# SW6106_A_B_C_MCU_LED.net
KiCad netlist of a schematic drawn in Altium Designer
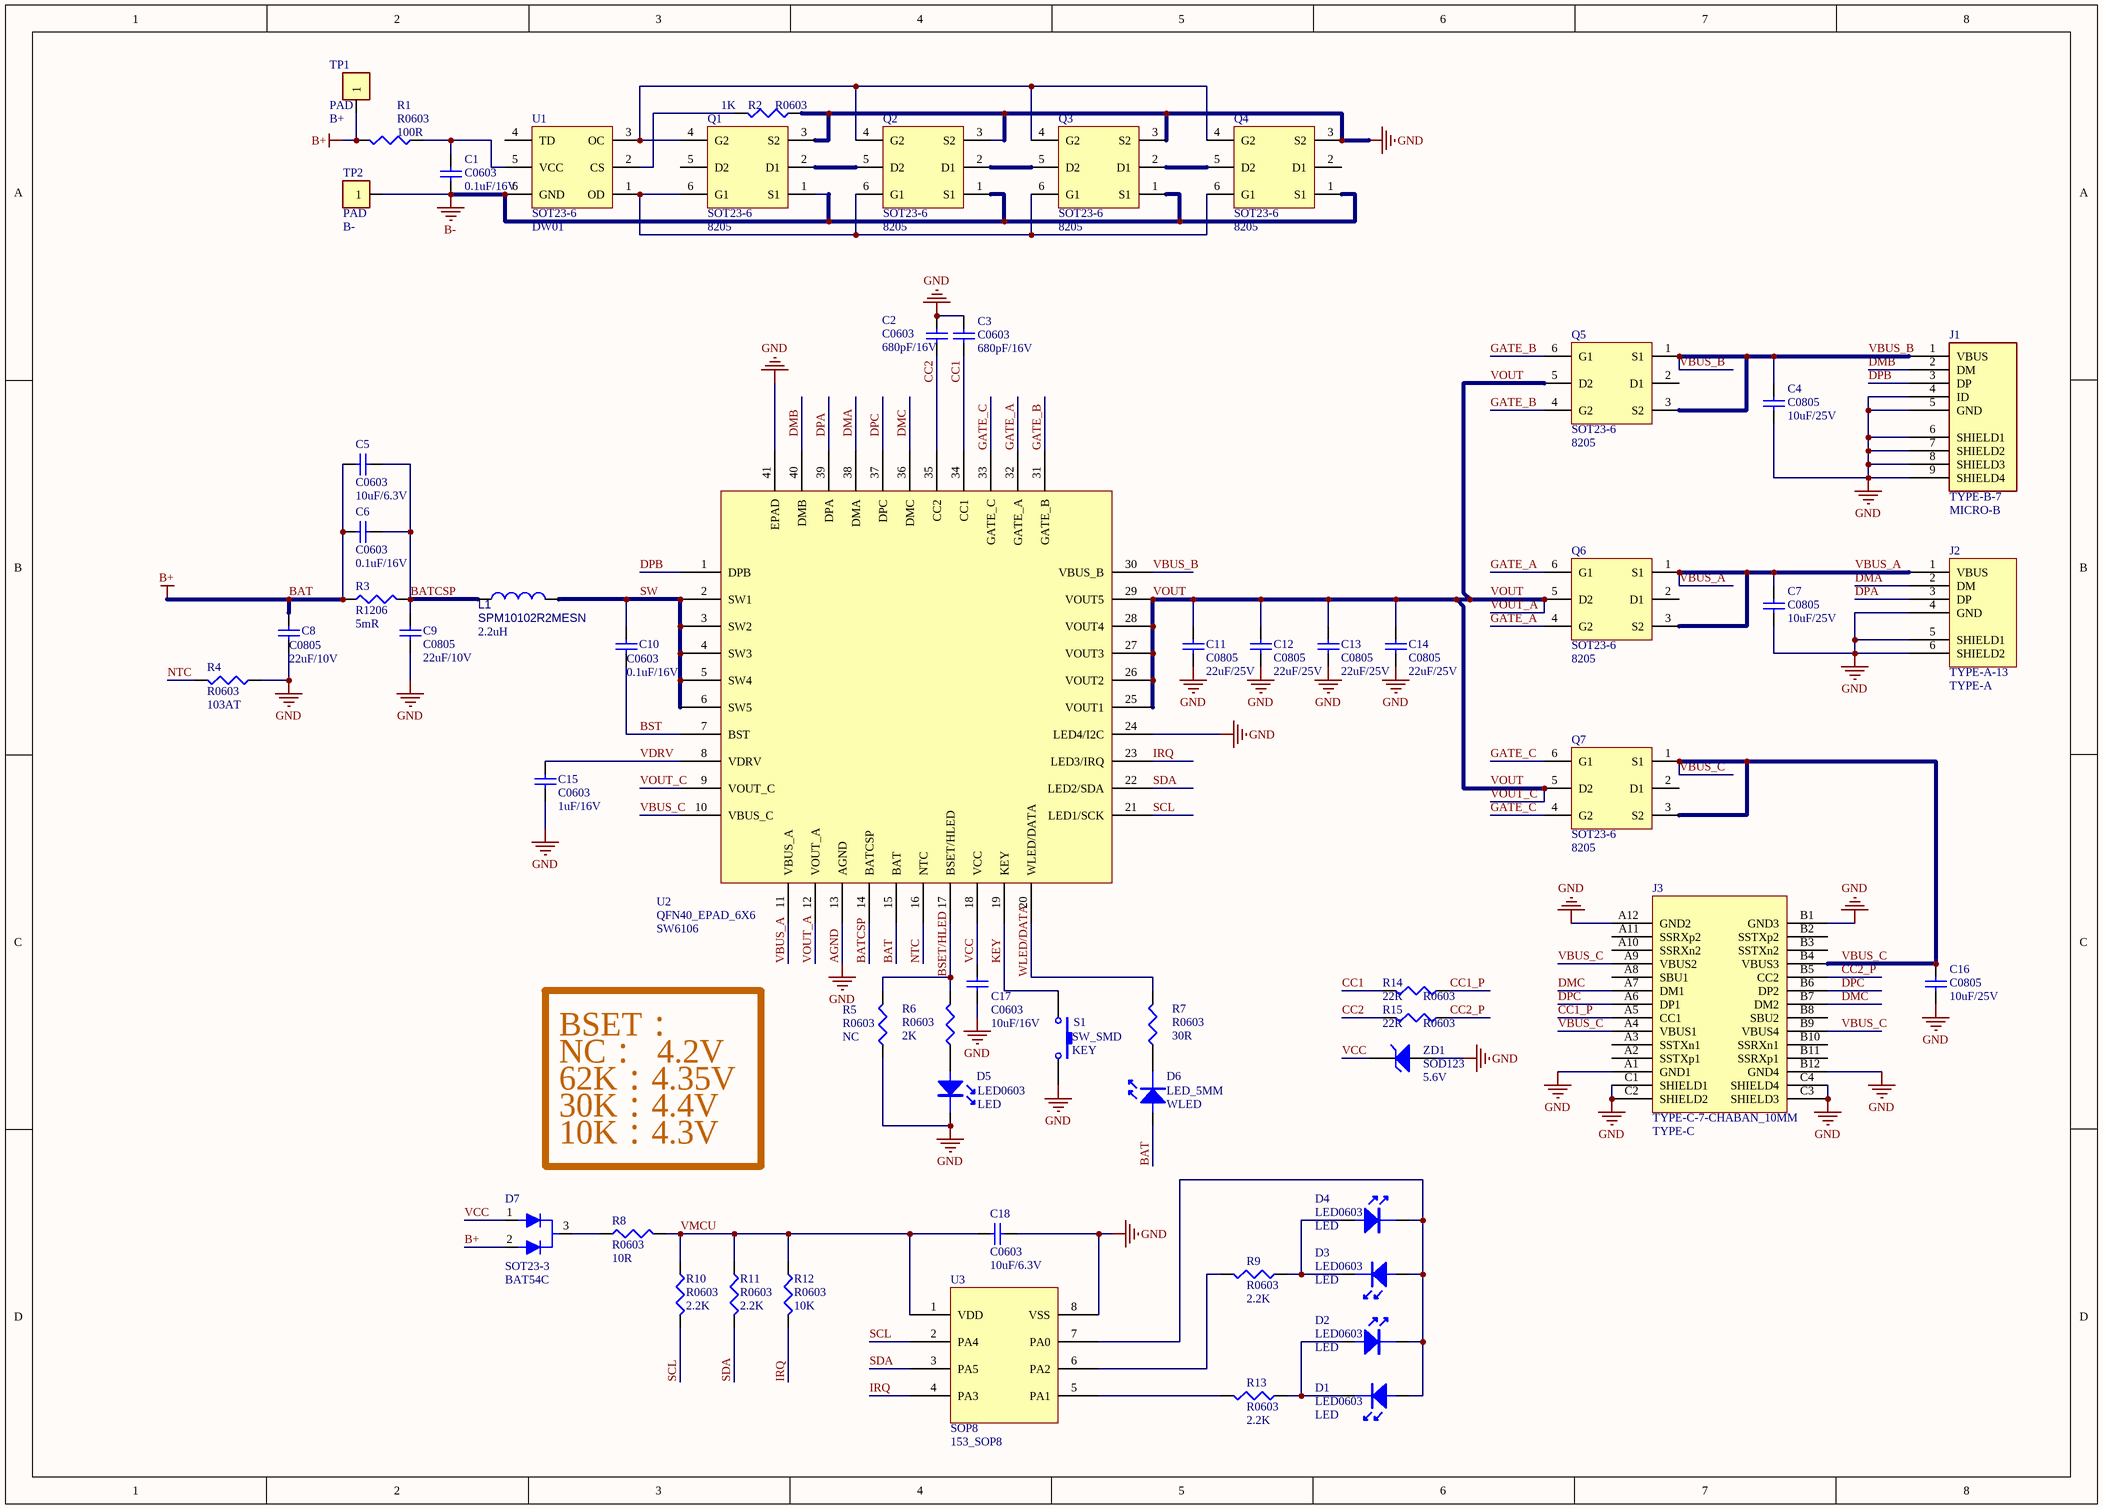
[diagram p0: SW6106+A+B+C+MCU+LED.SchDoc]

(export (version "E")
  (design (tool "Eeschema 10.0.6"))
  (components
    (comp (ref "C1")
      (value "C0603")
      (footprint "C0603")
      (description "Capacitor")
      (fields (field (name "ALTIUM_VALUE") "0.1uF/16V") (field (name "PUBLISHER") "Altium Limited"))
      (libsource (lib "*") (part "Cap"))
    )
    (comp (ref "C2")
      (value "C0603")
      (footprint "C0603")
      (description "Capacitor")
      (fields (field (name "ALTIUM_VALUE") "680pF/16V") (field (name "PUBLISHER") "Altium Limited"))
      (libsource (lib "*") (part "CAP0603"))
    )
    (comp (ref "C3")
      (value "C0603")
      (footprint "C0603")
      (description "Capacitor")
      (fields (field (name "ALTIUM_VALUE") "680pF/16V") (field (name "PUBLISHER") "Altium Limited"))
      (libsource (lib "*") (part "CAP0603"))
    )
    (comp (ref "C4")
      (value "C0805")
      (footprint "C0805")
      (description "Capacitor")
      (fields (field (name "ALTIUM_VALUE") "10uF/25V") (field (name "PUBLISHER") "Altium Limited"))
      (libsource (lib "*") (part "CAP0603"))
    )
    (comp (ref "C5")
      (value "C0603")
      (footprint "C0603")
      (description "Capacitor")
      (fields (field (name "ALTIUM_VALUE") "10uF/6.3V") (field (name "PUBLISHER") "Altium Limited"))
      (libsource (lib "*") (part "CAP0603"))
    )
    (comp (ref "C6")
      (value "C0603")
      (footprint "C0603")
      (description "Capacitor")
      (fields (field (name "ALTIUM_VALUE") "0.1uF/16V") (field (name "PUBLISHER") "Altium Limited"))
      (libsource (lib "*") (part "CAP0603"))
    )
    (comp (ref "C7")
      (value "C0805")
      (footprint "C0805")
      (description "Capacitor")
      (fields (field (name "ALTIUM_VALUE") "10uF/25V") (field (name "PUBLISHER") "Altium Limited"))
      (libsource (lib "*") (part "CAP0603"))
    )
    (comp (ref "C8")
      (value "C0805")
      (footprint "C0805")
      (description "Capacitor")
      (fields (field (name "ALTIUM_VALUE") "22uF/10V") (field (name "PUBLISHER") "Altium Limited"))
      (libsource (lib "*") (part "CAP0805"))
    )
    (comp (ref "C9")
      (value "C0805")
      (footprint "C0805")
      (description "Capacitor")
      (fields (field (name "ALTIUM_VALUE") "22uF/10V") (field (name "PUBLISHER") "Altium Limited"))
      (libsource (lib "*") (part "CAP0805"))
    )
    (comp (ref "C10")
      (value "C0603")
      (footprint "C0603")
      (description "Capacitor")
      (fields (field (name "ALTIUM_VALUE") "0.1uF/16V") (field (name "PUBLISHER") "Altium Limited"))
      (libsource (lib "*") (part "CAP0603"))
    )
    (comp (ref "C11")
      (value "C0805")
      (footprint "C0805")
      (description "Capacitor")
      (fields (field (name "ALTIUM_VALUE") "22uF/25V") (field (name "PUBLISHER") "Altium Limited"))
      (libsource (lib "*") (part "CAP0805"))
    )
    (comp (ref "C12")
      (value "C0805")
      (footprint "C0805")
      (description "Capacitor")
      (fields (field (name "ALTIUM_VALUE") "22uF/25V") (field (name "PUBLISHER") "Altium Limited"))
      (libsource (lib "*") (part "CAP0805"))
    )
    (comp (ref "C13")
      (value "C0805")
      (footprint "C0805")
      (description "Capacitor")
      (fields (field (name "ALTIUM_VALUE") "22uF/25V") (field (name "PUBLISHER") "Altium Limited"))
      (libsource (lib "*") (part "CAP0805"))
    )
    (comp (ref "C14")
      (value "C0805")
      (footprint "C0805")
      (description "Capacitor")
      (fields (field (name "ALTIUM_VALUE") "22uF/25V") (field (name "PUBLISHER") "Altium Limited"))
      (libsource (lib "*") (part "CAP0805"))
    )
    (comp (ref "C15")
      (value "C0603")
      (footprint "C0603")
      (description "Capacitor")
      (fields (field (name "ALTIUM_VALUE") "1uF/16V") (field (name "PUBLISHER") "Altium Limited"))
      (libsource (lib "*") (part "CAP0603"))
    )
    (comp (ref "C16")
      (value "C0805")
      (footprint "C0805")
      (description "Capacitor")
      (fields (field (name "ALTIUM_VALUE") "10uF/25V") (field (name "PUBLISHER") "Altium Limited"))
      (libsource (lib "*") (part "CAP0603"))
    )
    (comp (ref "C17")
      (value "C0603")
      (footprint "C0603")
      (description "Capacitor")
      (fields (field (name "ALTIUM_VALUE") "10uF/16V") (field (name "PUBLISHER") "Altium Limited"))
      (libsource (lib "*") (part "CAP0603"))
    )
    (comp (ref "C18")
      (value "C0603")
      (footprint "C0603")
      (description "Capacitor")
      (fields (field (name "ALTIUM_VALUE") "10uF/6.3V") (field (name "PUBLISHER") "Altium Limited"))
      (libsource (lib "*") (part "CAP0603"))
    )
    (comp (ref "D1") (value "LED") (footprint "LED0603") (libsource (lib "*") (part "LED")))
    (comp (ref "D2") (value "LED") (footprint "LED0603") (libsource (lib "*") (part "LED")))
    (comp (ref "D3") (value "LED") (footprint "LED0603") (libsource (lib "*") (part "LED")))
    (comp (ref "D4") (value "LED") (footprint "LED0603") (libsource (lib "*") (part "LED")))
    (comp (ref "D5") (value "LED") (footprint "LED0603") (libsource (lib "*") (part "LED")))
    (comp (ref "D6")
      (value "WLED")
      (footprint "LED_5MM")
      (fields (field (name "FOOTPRINF") "LED_5MM") (field (name "Comment") "LED_5MM"))
      (libsource (lib "*") (part "LED"))
    )
    (comp (ref "D7") (value "BAT54C") (footprint "SOT23-3") (libsource (lib "Schlib1-2012") (part "D3")))
    (comp (ref "J1")
      (value "MICRO-B")
      (footprint "TYPE-B-7")
      (fields (field (name "FOOTPRINTF") "TYPE-B-7") (field (name "Comment") "USB_MICRO_B"))
      (libsource (lib "*") (part "USB_MICRO_B"))
    )
    (comp (ref "J2")
      (value "TYPE-A")
      (footprint "TYPE-A-13")
      (fields (field (name "FOOTPRINF") "TYPE-A-13") (field (name "Comment") "TYPE-A-1"))
      (libsource (lib "*") (part "TYPE-A-1"))
    )
    (comp (ref "J3")
      (value "TYPE-C")
      (footprint "TYPE-C-7-CHABAN_10MM")
      (libsource (lib "*") (part "TYPE-C"))
    )
    (comp (ref "L1")
      (value "SPM10102R2MESN")
      (footprint "INDUCTOR_SPM1010")
      (fields (field (name "ALTIUM_VALUE") "2.2uH"))
      (libsource (lib "*") (part "INDUCTOR"))
    )
    (comp (ref "Q1")
      (value "8205")
      (footprint "SOT23-6")
      (fields (field (name "FOOTPRINF") "SOT23-6"))
      (libsource (lib "") (part "8205B_1"))
    )
    (comp (ref "Q2")
      (value "8205")
      (footprint "SOT23-6")
      (fields (field (name "FOOTPRINF") "SOT23-6"))
      (libsource (lib "") (part "8205B_1"))
    )
    (comp (ref "Q3")
      (value "8205")
      (footprint "SOT23-6")
      (fields (field (name "FOOTPRINF") "SOT23-6"))
      (libsource (lib "") (part "8205B_1"))
    )
    (comp (ref "Q4")
      (value "8205")
      (footprint "SOT23-6")
      (fields (field (name "FOOTPRINF") "SOT23-6"))
      (libsource (lib "") (part "8205B_1"))
    )
    (comp (ref "Q5")
      (value "8205")
      (footprint "SOT23-6")
      (fields (field (name "FOOTPRINF") "SOT23-6"))
      (libsource (lib "*") (part "8205B"))
    )
    (comp (ref "Q6")
      (value "8205")
      (footprint "SOT23-6")
      (fields (field (name "FOOTPRINF") "SOT23-6"))
      (libsource (lib "*") (part "8205B"))
    )
    (comp (ref "Q7")
      (value "8205")
      (footprint "SOT23-6")
      (fields (field (name "FOOTPRINF") "SOT23-6"))
      (libsource (lib "*") (part "8205B"))
    )
    (comp (ref "R1")
      (value "R0603")
      (footprint "R0603")
      (description "Resistor")
      (fields (field (name "ALTIUM_VALUE") "100R") (field (name "PUBLISHER") "Altium Limited"))
      (libsource (lib "*") (part "Res3"))
    )
    (comp (ref "R2")
      (value "R0603")
      (footprint "R0603")
      (description "Resistor")
      (fields (field (name "ALTIUM_VALUE") "1K") (field (name "PUBLISHER") "Altium Limited"))
      (libsource (lib "*") (part "Res3"))
    )
    (comp (ref "R3")
      (value "R1206")
      (footprint "R1206")
      (description "Resistor")
      (fields (field (name "ALTIUM_VALUE") "5mR") (field (name "PUBLISHER") "Altium Limited"))
      (libsource (lib "*") (part "RES"))
    )
    (comp (ref "R4")
      (value "R0603")
      (footprint "R0603")
      (description "Resistor")
      (fields (field (name "ALTIUM_VALUE") "103AT") (field (name "PUBLISHER") "Altium Limited"))
      (libsource (lib "*") (part "RES"))
    )
    (comp (ref "R5")
      (value "R0603")
      (footprint "R0603")
      (description "Resistor")
      (fields (field (name "ALTIUM_VALUE") "NC") (field (name "PUBLISHER") "Altium Limited"))
      (libsource (lib "*") (part "RES"))
    )
    (comp (ref "R6")
      (value "R0603")
      (footprint "R0603")
      (description "Resistor")
      (fields (field (name "ALTIUM_VALUE") "2K") (field (name "PUBLISHER") "Altium Limited"))
      (libsource (lib "*") (part "RES"))
    )
    (comp (ref "R7")
      (value "R0603")
      (footprint "R0603")
      (description "Resistor")
      (fields (field (name "ALTIUM_VALUE") "30R") (field (name "PUBLISHER") "Altium Limited"))
      (libsource (lib "*") (part "RES"))
    )
    (comp (ref "R8")
      (value "R0603")
      (footprint "R0603")
      (description "Resistor")
      (fields (field (name "ALTIUM_VALUE") "10R") (field (name "PUBLISHER") "Altium Limited"))
      (libsource (lib "*") (part "RES"))
    )
    (comp (ref "R9")
      (value "R0603")
      (footprint "R0603")
      (description "Resistor")
      (fields (field (name "ALTIUM_VALUE") "2.2K") (field (name "PUBLISHER") "Altium Limited"))
      (libsource (lib "*") (part "RES"))
    )
    (comp (ref "R10")
      (value "R0603")
      (footprint "R0603")
      (description "Resistor")
      (fields (field (name "ALTIUM_VALUE") "2.2K") (field (name "PUBLISHER") "Altium Limited"))
      (libsource (lib "*") (part "RES"))
    )
    (comp (ref "R11")
      (value "R0603")
      (footprint "R0603")
      (description "Resistor")
      (fields (field (name "ALTIUM_VALUE") "2.2K") (field (name "PUBLISHER") "Altium Limited"))
      (libsource (lib "*") (part "RES"))
    )
    (comp (ref "R12")
      (value "R0603")
      (footprint "R0603")
      (description "Resistor")
      (fields (field (name "ALTIUM_VALUE") "10K") (field (name "PUBLISHER") "Altium Limited"))
      (libsource (lib "*") (part "RES"))
    )
    (comp (ref "R13")
      (value "R0603")
      (footprint "R0603")
      (description "Resistor")
      (fields (field (name "ALTIUM_VALUE") "2.2K") (field (name "PUBLISHER") "Altium Limited"))
      (libsource (lib "*") (part "RES"))
    )
    (comp (ref "R14")
      (value "R0603")
      (footprint "R0603")
      (description "Resistor")
      (fields (field (name "ALTIUM_VALUE") "22R") (field (name "PUBLISHER") "Altium Limited"))
      (libsource (lib "*") (part "RES"))
    )
    (comp (ref "R15")
      (value "R0603")
      (footprint "R0603")
      (description "Resistor")
      (fields (field (name "ALTIUM_VALUE") "22R") (field (name "PUBLISHER") "Altium Limited"))
      (libsource (lib "*") (part "RES"))
    )
    (comp (ref "S1")
      (value "KEY")
      (footprint "SW_SMD")
      (fields (field (name "FOOTPRINF") "SW_SMD"))
      (libsource (lib "*") (part "SW K"))
    )
    (comp (ref "TP1") (value "B+") (footprint "PAD") (libsource (lib "*") (part "Test Point")))
    (comp (ref "TP2") (value "B-") (footprint "PAD") (libsource (lib "") (part "Test Point_1")))
    (comp (ref "U1")
      (value "DW01")
      (footprint "SOT23-6")
      (fields (field (name "FOOTPRINF") "SOT23-6"))
      (libsource (lib "*") (part "DW01"))
    )
    (comp (ref "U2")
      (value "SW6106")
      (footprint "QFN40_EPAD_6X6")
      (libsource (lib "TEST") (part "SW6106_AFC"))
    )
    (comp (ref "U3") (value "153_SOP8") (footprint "SOP8") (libsource (lib "TEST") (part "153_SOP8")))
    (comp (ref "ZD1")
      (value "SOD123")
      (footprint "SOD-123")
      (description "Zener Diode")
      (fields (field (name "ALTIUM_UNNAMED_1") "5.6V"))
      (libsource (lib "Miscellaneous Devices") (part "D Zener"))
    )
  )
  (nets
    (net (code "1") (name "/BATCSP") (class "Default")
      (node (ref "C5") (pin "2") (pinfunction "2_2") (pintype "passive"))
      (node (ref "C6") (pin "2") (pinfunction "2_2") (pintype "passive"))
      (node (ref "C9") (pin "2") (pinfunction "2_2") (pintype "passive"))
      (node (ref "L1") (pin "1") (pinfunction "1_1") (pintype "passive"))
      (node (ref "R3") (pin "2") (pinfunction "2_2") (pintype "passive"))
      (node (ref "U2") (pin "14") (pinfunction "BATCSP_14") (pintype "passive"))
    )
    (net (code "2") (name "/BSET{slash}HLED") (class "Default")
      (node (ref "R5") (pin "2") (pinfunction "2_2") (pintype "passive"))
      (node (ref "R6") (pin "2") (pinfunction "2_2") (pintype "passive"))
      (node (ref "U2") (pin "17") (pinfunction "BSET/HLED_17") (pintype "passive"))
    )
    (net (code "3") (name "/BST") (class "Default")
      (node (ref "C10") (pin "1") (pinfunction "1_1") (pintype "passive"))
      (node (ref "U2") (pin "7") (pinfunction "BST_7") (pintype "passive"))
    )
    (net (code "4") (name "/CC1") (class "Default")
      (node (ref "C3") (pin "1") (pinfunction "1_1") (pintype "passive"))
      (node (ref "R14") (pin "2") (pinfunction "2_2") (pintype "passive"))
      (node (ref "U2") (pin "34") (pinfunction "CC1_34") (pintype "passive"))
    )
    (net (code "5") (name "/CC1_P") (class "Default")
      (node (ref "J3") (pin "A5") (pinfunction "CC1_A5") (pintype "passive"))
      (node (ref "R14") (pin "1") (pinfunction "1_1") (pintype "passive"))
    )
    (net (code "6") (name "/CC2") (class "Default")
      (node (ref "C2") (pin "1") (pinfunction "1_1") (pintype "passive"))
      (node (ref "R15") (pin "2") (pinfunction "2_2") (pintype "passive"))
      (node (ref "U2") (pin "35") (pinfunction "CC2_35") (pintype "passive"))
    )
    (net (code "7") (name "/CC2_P") (class "Default")
      (node (ref "J3") (pin "B5") (pinfunction "CC2_B5") (pintype "passive"))
      (node (ref "R15") (pin "1") (pinfunction "1_1") (pintype "passive"))
    )
    (net (code "8") (name "/DMA") (class "Default")
      (node (ref "J2") (pin "2") (pinfunction "DM_2") (pintype "passive"))
      (node (ref "U2") (pin "38") (pinfunction "DMA_38") (pintype "passive"))
    )
    (net (code "9") (name "/DMB") (class "Default")
      (node (ref "J1") (pin "2") (pinfunction "DM_2") (pintype "passive"))
      (node (ref "U2") (pin "40") (pinfunction "DMB_40") (pintype "passive"))
    )
    (net (code "10") (name "/DMC") (class "Default")
      (node (ref "J3") (pin "A7") (pinfunction "DM1_A7") (pintype "passive"))
      (node (ref "J3") (pin "B7") (pinfunction "DM2_B7") (pintype "passive"))
      (node (ref "U2") (pin "36") (pinfunction "DMC_36") (pintype "passive"))
    )
    (net (code "11") (name "/DPA") (class "Default")
      (node (ref "J2") (pin "3") (pinfunction "DP_3") (pintype "passive"))
      (node (ref "U2") (pin "39") (pinfunction "DPA_39") (pintype "passive"))
    )
    (net (code "12") (name "/DPB") (class "Default")
      (node (ref "J1") (pin "3") (pinfunction "DP_3") (pintype "passive"))
      (node (ref "U2") (pin "1") (pinfunction "DPB_1") (pintype "passive"))
    )
    (net (code "13") (name "/DPC") (class "Default")
      (node (ref "J3") (pin "A6") (pinfunction "DP1_A6") (pintype "passive"))
      (node (ref "J3") (pin "B6") (pinfunction "DP2_B6") (pintype "passive"))
      (node (ref "U2") (pin "37") (pinfunction "DPC_37") (pintype "passive"))
    )
    (net (code "14") (name "/GATE_A") (class "Default")
      (node (ref "Q6") (pin "4") (pinfunction "G2_4") (pintype "passive"))
      (node (ref "Q6") (pin "6") (pinfunction "G1_6") (pintype "passive"))
      (node (ref "U2") (pin "32") (pinfunction "GATE_A_32") (pintype "passive"))
    )
    (net (code "15") (name "/GATE_B") (class "Default")
      (node (ref "Q5") (pin "4") (pinfunction "G2_4") (pintype "passive"))
      (node (ref "Q5") (pin "6") (pinfunction "G1_6") (pintype "passive"))
      (node (ref "U2") (pin "31") (pinfunction "GATE_B_31") (pintype "passive"))
    )
    (net (code "16") (name "/GATE_C") (class "Default")
      (node (ref "Q7") (pin "4") (pinfunction "G2_4") (pintype "passive"))
      (node (ref "Q7") (pin "6") (pinfunction "G1_6") (pintype "passive"))
      (node (ref "U2") (pin "33") (pinfunction "GATE_C_33") (pintype "passive"))
    )
    (net (code "17") (name "/IRQ") (class "Default")
      (node (ref "R12") (pin "2") (pinfunction "2_2") (pintype "passive"))
      (node (ref "U2") (pin "23") (pinfunction "LED3/IRQ_23") (pintype "passive"))
      (node (ref "U3") (pin "4") (pinfunction "PA3_4") (pintype "passive"))
    )
    (net (code "18") (name "/KEY") (class "Default")
      (node (ref "S1") (pin "1") (pinfunction "1_1") (pintype "passive"))
      (node (ref "U2") (pin "19") (pinfunction "KEY_19") (pintype "passive"))
    )
    (net (code "19") (name "/NTC") (class "Default")
      (node (ref "R4") (pin "2") (pinfunction "2_2") (pintype "passive"))
      (node (ref "U2") (pin "16") (pinfunction "NTC_16") (pintype "passive"))
    )
    (net (code "20") (name "/SCL") (class "Default")
      (node (ref "R10") (pin "2") (pinfunction "2_2") (pintype "passive"))
      (node (ref "U2") (pin "21") (pinfunction "LED1/SCK_21") (pintype "passive"))
      (node (ref "U3") (pin "2") (pinfunction "PA4_2") (pintype "passive"))
    )
    (net (code "21") (name "/SDA") (class "Default")
      (node (ref "R11") (pin "2") (pinfunction "2_2") (pintype "passive"))
      (node (ref "U2") (pin "22") (pinfunction "LED2/SDA_22") (pintype "passive"))
      (node (ref "U3") (pin "3") (pinfunction "PA5_3") (pintype "passive"))
    )
    (net (code "22") (name "/SW") (class "Default")
      (node (ref "C10") (pin "2") (pinfunction "2_2") (pintype "passive"))
      (node (ref "L1") (pin "2") (pinfunction "2_2") (pintype "passive"))
      (node (ref "U2") (pin "2") (pinfunction "SW1_2") (pintype "passive"))
      (node (ref "U2") (pin "3") (pinfunction "SW2_3") (pintype "passive"))
      (node (ref "U2") (pin "4") (pinfunction "SW3_4") (pintype "passive"))
      (node (ref "U2") (pin "5") (pinfunction "SW4_5") (pintype "passive"))
      (node (ref "U2") (pin "6") (pinfunction "SW5_6") (pintype "passive"))
    )
    (net (code "23") (name "/VBUS_A") (class "Default")
      (node (ref "C7") (pin "2") (pinfunction "2_2") (pintype "passive"))
      (node (ref "J2") (pin "1") (pinfunction "VBUS_1") (pintype "passive"))
      (node (ref "Q6") (pin "1") (pinfunction "S1_1") (pintype "passive"))
      (node (ref "Q6") (pin "3") (pinfunction "S2_3") (pintype "passive"))
      (node (ref "U2") (pin "11") (pinfunction "VBUS_A_11") (pintype "passive"))
    )
    (net (code "24") (name "/VBUS_B") (class "Default")
      (node (ref "C4") (pin "2") (pinfunction "2_2") (pintype "passive"))
      (node (ref "J1") (pin "1") (pinfunction "VBUS_1") (pintype "passive"))
      (node (ref "Q5") (pin "1") (pinfunction "S1_1") (pintype "passive"))
      (node (ref "Q5") (pin "3") (pinfunction "S2_3") (pintype "passive"))
      (node (ref "U2") (pin "30") (pinfunction "VBUS_B_30") (pintype "passive"))
    )
    (net (code "25") (name "/VBUS_C") (class "Default")
      (node (ref "C16") (pin "2") (pinfunction "2_2") (pintype "passive"))
      (node (ref "J3") (pin "A4") (pinfunction "VBUS1_A4") (pintype "passive"))
      (node (ref "J3") (pin "A9") (pinfunction "VBUS2_A9") (pintype "passive"))
      (node (ref "J3") (pin "B4") (pinfunction "VBUS3_B4") (pintype "passive"))
      (node (ref "J3") (pin "B9") (pinfunction "VBUS4_B9") (pintype "passive"))
      (node (ref "Q7") (pin "1") (pinfunction "S1_1") (pintype "passive"))
      (node (ref "Q7") (pin "3") (pinfunction "S2_3") (pintype "passive"))
      (node (ref "U2") (pin "10") (pinfunction "VBUS_C_10") (pintype "passive"))
    )
    (net (code "26") (name "/VCC") (class "Default")
      (node (ref "C17") (pin "2") (pinfunction "2_2") (pintype "passive"))
      (node (ref "D7") (pin "1") (pintype "passive"))
      (node (ref "U2") (pin "18") (pinfunction "VCC_18") (pintype "passive"))
      (node (ref "ZD1") (pin "2") (pinfunction "K_2") (pintype "passive"))
    )
    (net (code "27") (name "/VDRV") (class "Default")
      (node (ref "C15") (pin "2") (pinfunction "2_2") (pintype "passive"))
      (node (ref "U2") (pin "8") (pinfunction "VDRV_8") (pintype "passive"))
    )
    (net (code "28") (name "/VMCU") (class "Default")
      (node (ref "C18") (pin "1") (pinfunction "1_1") (pintype "passive"))
      (node (ref "R10") (pin "1") (pinfunction "1_1") (pintype "passive"))
      (node (ref "R11") (pin "1") (pinfunction "1_1") (pintype "passive"))
      (node (ref "R12") (pin "1") (pinfunction "1_1") (pintype "passive"))
      (node (ref "R8") (pin "2") (pinfunction "2_2") (pintype "passive"))
      (node (ref "U3") (pin "1") (pinfunction "VDD_1") (pintype "passive"))
    )
    (net (code "29") (name "/VOUT") (class "Default")
      (node (ref "C11") (pin "2") (pinfunction "2_2") (pintype "passive"))
      (node (ref "C12") (pin "2") (pinfunction "2_2") (pintype "passive"))
      (node (ref "C13") (pin "2") (pinfunction "2_2") (pintype "passive"))
      (node (ref "C14") (pin "2") (pinfunction "2_2") (pintype "passive"))
      (node (ref "Q5") (pin "5") (pinfunction "D2_5") (pintype "passive"))
      (node (ref "Q6") (pin "5") (pinfunction "D2_5") (pintype "passive"))
      (node (ref "Q7") (pin "5") (pinfunction "D2_5") (pintype "passive"))
      (node (ref "U2") (pin "12") (pinfunction "VOUT_A_12") (pintype "passive"))
      (node (ref "U2") (pin "25") (pinfunction "VOUT1_25") (pintype "passive"))
      (node (ref "U2") (pin "26") (pinfunction "VOUT2_26") (pintype "passive"))
      (node (ref "U2") (pin "27") (pinfunction "VOUT3_27") (pintype "passive"))
      (node (ref "U2") (pin "28") (pinfunction "VOUT4_28") (pintype "passive"))
      (node (ref "U2") (pin "29") (pinfunction "VOUT5_29") (pintype "passive"))
      (node (ref "U2") (pin "9") (pinfunction "VOUT_C_9") (pintype "passive"))
    )
    (net (code "30") (name "/WLED{slash}DATA") (class "Default")
      (node (ref "R7") (pin "2") (pinfunction "2_2") (pintype "passive"))
      (node (ref "U2") (pin "20") (pinfunction "WLED/DATA_20") (pintype "passive"))
    )
    (net (code "31") (name "B+") (class "Default")
      (node (ref "C5") (pin "1") (pinfunction "1_1") (pintype "passive"))
      (node (ref "C6") (pin "1") (pinfunction "1_1") (pintype "passive"))
      (node (ref "C8") (pin "2") (pinfunction "2_2") (pintype "passive"))
      (node (ref "D6") (pin "1") (pinfunction "A_1") (pintype "passive"))
      (node (ref "D7") (pin "2") (pintype "passive"))
      (node (ref "R1") (pin "2") (pinfunction "2_2") (pintype "passive"))
      (node (ref "R3") (pin "1") (pinfunction "1_1") (pintype "passive"))
      (node (ref "TP1") (pin "1") (pinfunction "1_1") (pintype "passive"))
      (node (ref "U2") (pin "15") (pinfunction "BAT_15") (pintype "passive"))
    )
    (net (code "32") (name "B-") (class "Default")
      (node (ref "C1") (pin "1") (pinfunction "1_1") (pintype "passive"))
      (node (ref "Q1") (pin "1") (pinfunction "S1_1") (pintype "passive"))
      (node (ref "Q2") (pin "1") (pinfunction "S1_1") (pintype "passive"))
      (node (ref "Q3") (pin "1") (pinfunction "S1_1") (pintype "passive"))
      (node (ref "Q4") (pin "1") (pinfunction "S1_1") (pintype "passive"))
      (node (ref "TP2") (pin "1") (pinfunction "1_1") (pintype "passive"))
      (node (ref "U1") (pin "6") (pinfunction "GND_6") (pintype "passive"))
    )
    (net (code "33") (name "GND") (class "Default")
      (node (ref "C11") (pin "1") (pinfunction "1_1") (pintype "passive"))
      (node (ref "C12") (pin "1") (pinfunction "1_1") (pintype "passive"))
      (node (ref "C13") (pin "1") (pinfunction "1_1") (pintype "passive"))
      (node (ref "C14") (pin "1") (pinfunction "1_1") (pintype "passive"))
      (node (ref "C15") (pin "1") (pinfunction "1_1") (pintype "passive"))
      (node (ref "C16") (pin "1") (pinfunction "1_1") (pintype "passive"))
      (node (ref "C17") (pin "1") (pinfunction "1_1") (pintype "passive"))
      (node (ref "C18") (pin "2") (pinfunction "2_2") (pintype "passive"))
      (node (ref "C2") (pin "2") (pinfunction "2_2") (pintype "passive"))
      (node (ref "C3") (pin "2") (pinfunction "2_2") (pintype "passive"))
      (node (ref "C4") (pin "1") (pinfunction "1_1") (pintype "passive"))
      (node (ref "C7") (pin "1") (pinfunction "1_1") (pintype "passive"))
      (node (ref "C8") (pin "1") (pinfunction "1_1") (pintype "passive"))
      (node (ref "C9") (pin "1") (pinfunction "1_1") (pintype "passive"))
      (node (ref "D5") (pin "2") (pinfunction "K_2") (pintype "passive"))
      (node (ref "J1") (pin "4") (pinfunction "ID_4") (pintype "passive"))
      (node (ref "J1") (pin "5") (pinfunction "GND_5") (pintype "passive"))
      (node (ref "J1") (pin "6") (pinfunction "SHIELD1_6") (pintype "passive"))
      (node (ref "J1") (pin "7") (pinfunction "SHIELD2_7") (pintype "passive"))
      (node (ref "J1") (pin "8") (pinfunction "SHIELD3_8") (pintype "passive"))
      (node (ref "J1") (pin "9") (pinfunction "SHIELD4_9") (pintype "passive"))
      (node (ref "J2") (pin "4") (pinfunction "GND_4") (pintype "passive"))
      (node (ref "J2") (pin "5") (pinfunction "SHIELD1_5") (pintype "passive"))
      (node (ref "J2") (pin "6") (pinfunction "SHIELD2_6") (pintype "passive"))
      (node (ref "J3") (pin "A1") (pinfunction "GND1_A1") (pintype "passive"))
      (node (ref "J3") (pin "A12") (pinfunction "GND2_A12") (pintype "passive"))
      (node (ref "J3") (pin "B1") (pinfunction "GND3_B1") (pintype "passive"))
      (node (ref "J3") (pin "B12") (pinfunction "GND4_B12") (pintype "passive"))
      (node (ref "J3") (pin "C1") (pinfunction "SHIELD1_C1") (pintype "passive"))
      (node (ref "J3") (pin "C2") (pinfunction "SHIELD2_C2") (pintype "passive"))
      (node (ref "J3") (pin "C3") (pinfunction "SHIELD3_C3") (pintype "passive"))
      (node (ref "J3") (pin "C4") (pinfunction "SHIELD4_C4") (pintype "passive"))
      (node (ref "Q1") (pin "3") (pinfunction "S2_3") (pintype "passive"))
      (node (ref "Q2") (pin "3") (pinfunction "S2_3") (pintype "passive"))
      (node (ref "Q3") (pin "3") (pinfunction "S2_3") (pintype "passive"))
      (node (ref "Q4") (pin "3") (pinfunction "S2_3") (pintype "passive"))
      (node (ref "R2") (pin "1") (pinfunction "1_1") (pintype "passive"))
      (node (ref "R4") (pin "1") (pinfunction "1_1") (pintype "passive"))
      (node (ref "R5") (pin "1") (pinfunction "1_1") (pintype "passive"))
      (node (ref "S1") (pin "2") (pinfunction "2_2") (pintype "passive"))
      (node (ref "U2") (pin "13") (pinfunction "AGND_13") (pintype "passive"))
      (node (ref "U2") (pin "24") (pinfunction "LED4/I2C_24") (pintype "passive"))
      (node (ref "U2") (pin "41") (pinfunction "EPAD_41") (pintype "passive"))
      (node (ref "U3") (pin "8") (pinfunction "VSS_8") (pintype "passive"))
      (node (ref "ZD1") (pin "1") (pinfunction "A_1") (pintype "passive"))
    )
    (net (code "34") (name "Net-(D1-A)") (class "Default")
      (node (ref "D1") (pin "1") (pinfunction "A_1") (pintype "passive"))
      (node (ref "D2") (pin "2") (pinfunction "K_2") (pintype "passive"))
      (node (ref "D3") (pin "1") (pinfunction "A_1") (pintype "passive"))
      (node (ref "D4") (pin "2") (pinfunction "K_2") (pintype "passive"))
      (node (ref "U3") (pin "7") (pinfunction "PA0_7") (pintype "passive"))
    )
    (net (code "35") (name "Net-(D1-K)") (class "Default")
      (node (ref "D1") (pin "2") (pinfunction "K_2") (pintype "passive"))
      (node (ref "D2") (pin "1") (pinfunction "A_1") (pintype "passive"))
      (node (ref "R13") (pin "1") (pinfunction "1_1") (pintype "passive"))
    )
    (net (code "36") (name "Net-(D3-K)") (class "Default")
      (node (ref "D3") (pin "2") (pinfunction "K_2") (pintype "passive"))
      (node (ref "D4") (pin "1") (pinfunction "A_1") (pintype "passive"))
      (node (ref "R9") (pin "1") (pinfunction "1_1") (pintype "passive"))
    )
    (net (code "37") (name "Net-(D5-A)") (class "Default")
      (node (ref "D5") (pin "1") (pinfunction "A_1") (pintype "passive"))
      (node (ref "R6") (pin "1") (pinfunction "1_1") (pintype "passive"))
    )
    (net (code "38") (name "Net-(D6-K)") (class "Default")
      (node (ref "D6") (pin "2") (pinfunction "K_2") (pintype "passive"))
      (node (ref "R7") (pin "1") (pinfunction "1_1") (pintype "passive"))
    )
    (net (code "39") (name "Net-(D7-Pad3)") (class "Default")
      (node (ref "D7") (pin "3") (pintype "passive"))
      (node (ref "R8") (pin "1") (pinfunction "1_1") (pintype "passive"))
    )
    (net (code "40") (name "Net-(Q1-D1)") (class "Default")
      (node (ref "Q1") (pin "2") (pinfunction "D1_2") (pintype "passive"))
      (node (ref "Q2") (pin "5") (pinfunction "D2_5") (pintype "passive"))
    )
    (net (code "41") (name "Net-(Q1-G1)") (class "Default")
      (node (ref "Q1") (pin "6") (pinfunction "G1_6") (pintype "passive"))
      (node (ref "Q2") (pin "6") (pinfunction "G1_6") (pintype "passive"))
      (node (ref "Q3") (pin "6") (pinfunction "G1_6") (pintype "passive"))
      (node (ref "Q4") (pin "6") (pinfunction "G1_6") (pintype "passive"))
      (node (ref "U1") (pin "1") (pinfunction "OD_1") (pintype "passive"))
    )
    (net (code "42") (name "Net-(Q1-G2)") (class "Default")
      (node (ref "Q1") (pin "4") (pinfunction "G2_4") (pintype "passive"))
      (node (ref "Q2") (pin "4") (pinfunction "G2_4") (pintype "passive"))
      (node (ref "Q3") (pin "4") (pinfunction "G2_4") (pintype "passive"))
      (node (ref "Q4") (pin "4") (pinfunction "G2_4") (pintype "passive"))
      (node (ref "U1") (pin "3") (pinfunction "OC_3") (pintype "passive"))
    )
    (net (code "43") (name "Net-(Q2-D1)") (class "Default")
      (node (ref "Q2") (pin "2") (pinfunction "D1_2") (pintype "passive"))
      (node (ref "Q3") (pin "5") (pinfunction "D2_5") (pintype "passive"))
    )
    (net (code "44") (name "Net-(Q3-D1)") (class "Default")
      (node (ref "Q3") (pin "2") (pinfunction "D1_2") (pintype "passive"))
      (node (ref "Q4") (pin "5") (pinfunction "D2_5") (pintype "passive"))
    )
    (net (code "45") (name "Net-(U1-CS)") (class "Default")
      (node (ref "R2") (pin "2") (pinfunction "2_2") (pintype "passive"))
      (node (ref "U1") (pin "2") (pinfunction "CS_2") (pintype "passive"))
    )
    (net (code "46") (name "Net-(U1-VCC)") (class "Default")
      (node (ref "C1") (pin "2") (pinfunction "2_2") (pintype "passive"))
      (node (ref "R1") (pin "1") (pinfunction "1_1") (pintype "passive"))
      (node (ref "U1") (pin "5") (pinfunction "VCC_5") (pintype "passive"))
    )
    (net (code "47") (name "Net-(U3-PA1)") (class "Default")
      (node (ref "R13") (pin "2") (pinfunction "2_2") (pintype "passive"))
      (node (ref "U3") (pin "5") (pinfunction "PA1_5") (pintype "passive"))
    )
    (net (code "48") (name "Net-(U3-PA2)") (class "Default")
      (node (ref "R9") (pin "2") (pinfunction "2_2") (pintype "passive"))
      (node (ref "U3") (pin "6") (pinfunction "PA2_6") (pintype "passive"))
    )
    (net (code "49") (name "unconnected-(J3-SBU1-PadA8)") (class "Default")
      (node (ref "J3") (pin "A8") (pinfunction "SBU1_A8") (pintype "passive"))
    )
    (net (code "50") (name "unconnected-(J3-SBU2-PadB8)") (class "Default")
      (node (ref "J3") (pin "B8") (pinfunction "SBU2_B8") (pintype "passive"))
    )
    (net (code "51") (name "unconnected-(J3-SSRXn1-PadB10)") (class "Default")
      (node (ref "J3") (pin "B10") (pinfunction "SSRXn1_B10") (pintype "passive"))
    )
    (net (code "52") (name "unconnected-(J3-SSRXn2-PadA10)") (class "Default")
      (node (ref "J3") (pin "A10") (pinfunction "SSRXn2_A10") (pintype "passive"))
    )
    (net (code "53") (name "unconnected-(J3-SSRXp1-PadB11)") (class "Default")
      (node (ref "J3") (pin "B11") (pinfunction "SSRXp1_B11") (pintype "passive"))
    )
    (net (code "54") (name "unconnected-(J3-SSRXp2-PadA11)") (class "Default")
      (node (ref "J3") (pin "A11") (pinfunction "SSRXp2_A11") (pintype "passive"))
    )
    (net (code "55") (name "unconnected-(J3-SSTXn1-PadA3)") (class "Default")
      (node (ref "J3") (pin "A3") (pinfunction "SSTXn1_A3") (pintype "passive"))
    )
    (net (code "56") (name "unconnected-(J3-SSTXn2-PadB3)") (class "Default")
      (node (ref "J3") (pin "B3") (pinfunction "SSTXn2_B3") (pintype "passive"))
    )
    (net (code "57") (name "unconnected-(J3-SSTXp1-PadA2)") (class "Default")
      (node (ref "J3") (pin "A2") (pinfunction "SSTXp1_A2") (pintype "passive"))
    )
    (net (code "58") (name "unconnected-(J3-SSTXp2-PadB2)") (class "Default")
      (node (ref "J3") (pin "B2") (pinfunction "SSTXp2_B2") (pintype "passive"))
    )
    (net (code "59") (name "unconnected-(Q1-D2-Pad5)") (class "Default")
      (node (ref "Q1") (pin "5") (pinfunction "D2_5") (pintype "passive"))
    )
    (net (code "60") (name "unconnected-(Q4-D1-Pad2)") (class "Default")
      (node (ref "Q4") (pin "2") (pinfunction "D1_2") (pintype "passive"))
    )
    (net (code "61") (name "unconnected-(Q5-D1-Pad2)") (class "Default")
      (node (ref "Q5") (pin "2") (pinfunction "D1_2") (pintype "passive"))
    )
    (net (code "62") (name "unconnected-(Q6-D1-Pad2)") (class "Default")
      (node (ref "Q6") (pin "2") (pinfunction "D1_2") (pintype "passive"))
    )
    (net (code "63") (name "unconnected-(Q7-D1-Pad2)") (class "Default")
      (node (ref "Q7") (pin "2") (pinfunction "D1_2") (pintype "passive"))
    )
    (net (code "64") (name "unconnected-(U1-TD-Pad4)") (class "Default")
      (node (ref "U1") (pin "4") (pinfunction "TD_4") (pintype "passive"))
    )
  )
)
